# POWER.net
KiCad netlist of a schematic drawn in Altium Designer
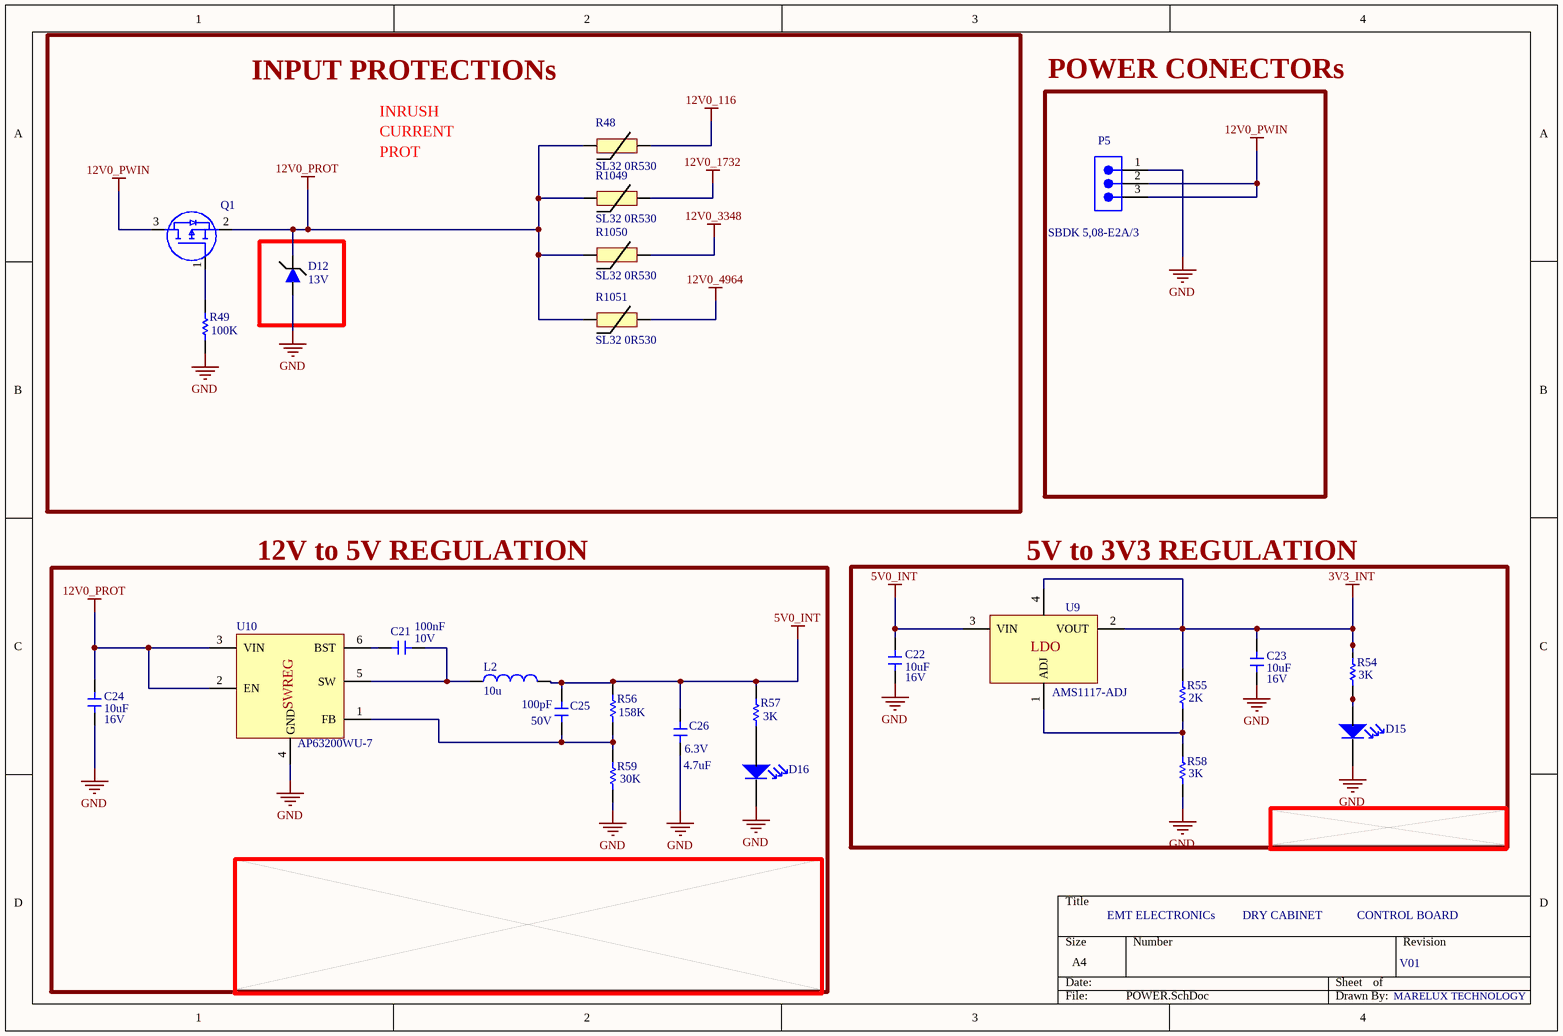
[diagram p0: POWER.SchDoc]

(export (version "E")
  (design (tool "Eeschema 10.0.6"))
  (components
    (comp (ref "C21")
      (value "100nF")
      (footprint "CAP_0402_CER")
      (description "Generic")
      (fields (field (name "PART NUMBER") "CL05B104KP5NNNC") (field (name "VOLTAGE") "10V"))
      (libsource (lib "MareLux24Lib") (part "CAP_GEN_CER"))
    )
    (comp (ref "C22")
      (value "10uF")
      (footprint "CAP_0805_CER")
      (description "10uF 0805 Ceramic Capacitor")
      (fields (field (name "PART NUMBER") "CL21A106KOQNNNE") (field (name "VOLTAGE") "16V"))
      (libsource (lib "MareLux24Lib") (part "CAP_GEN_CER"))
    )
    (comp (ref "C23")
      (value "10uF")
      (footprint "CAP_0805_CER")
      (description "10uF 0805 Ceramic Capacitor")
      (fields (field (name "PART NUMBER") "CL21A106KOQNNNE") (field (name "VOLTAGE") "16V"))
      (libsource (lib "MareLux24Lib") (part "CAP_GEN_CER"))
    )
    (comp (ref "C24")
      (value "10uF")
      (footprint "CAP_0805_CER")
      (description "10uF 0805 Ceramic Capacitor")
      (fields (field (name "PART NUMBER") "CL21A106KOQNNNE") (field (name "VOLTAGE") "16V"))
      (libsource (lib "MareLux24Lib") (part "CAP_GEN_CER"))
    )
    (comp (ref "C25")
      (value "100pF")
      (footprint "CAP_0402_CER")
      (description "Generic")
      (fields (field (name "PART NUMBER") "CC0402JRNPO9BN101") (field (name "VOLTAGE") "50V"))
      (libsource (lib "MareLux24Lib") (part "CAP_GEN_CER"))
    )
    (comp (ref "C26")
      (value "4.7uF")
      (footprint "CAP_0402_CER")
      (description "Generic")
      (fields (field (name "PART NUMBER") "CL10A475KP8NNNC") (field (name "VOLTAGE") "6.3V"))
      (libsource (lib "MareLux24Lib") (part "CAP_GEN_CER"))
    )
    (comp (ref "D12")
      (value "13V")
      (footprint "SOD-123F")
      (description "TVS DIODE 200W 14.4V-15.9V SOD-123")
      (fields (field (name "PART NUMBER") "SMF13A") (field (name "VOLTAGE") "14.4V"))
      (libsource (lib "MareLux24Lib") (part "SMF13A"))
    )
    (comp (ref "D15")
      (value "HSMM-C170")
      (footprint "LED_0805_SMD")
      (fields (field (name "VOLTAGE") "3.3V") (field (name "MANUFACTURER") "Broadcom"))
      (libsource (lib "MareLux24Lib") (part "LED_GEN"))
    )
    (comp (ref "D16")
      (value "HSMM-C170")
      (footprint "LED_0805_SMD")
      (fields (field (name "VOLTAGE") "3.3V") (field (name "MANUFACTURER") "Broadcom"))
      (libsource (lib "MareLux24Lib") (part "LED_GEN"))
    )
    (comp (ref "L2")
      (value "10u")
      (footprint "IND_YAGEO")
      (description "FIXED IND 10UH 4A 68 MOHM SMD")
      (fields (field (name "PART NUMBER") "BMRB00060630100MA1") (field (name "TOLERANCE") "±20%"))
      (libsource (lib "MareLux24Lib") (part "BMRB00060630100MA1"))
    )
    (comp (ref "P5")
      (value "SBDK 5,08-E2A/3")
      (footprint "691311500003")
      (description "WR-TBL Series 311 Open Vertical PCB Header, THT, pitch 5.08mm, 03p")
      (fields (field (name "MANUFACTURER") "Wurth Elektronik"))
      (libsource (lib "Altium_WR-TBL_Pluggable Connector (rev25b)") (part "691311500003"))
    )
    (comp (ref "Q1")
      (value "SQM110P06-8M9L_GE3")
      (footprint "SQM110P06_MOSFET")
      (description "P-Channel 60 V 110A (Tc) 230W (Tc) Surface Mount TO-263 (D2PAK)")
      (fields (field (name "VOLTAGE") "20 V") (field (name "POWER") "110A"))
      (libsource (lib "MareLux24Lib") (part "SQM110P06-8M9L_GE3"))
    )
    (comp (ref "R48")
      (value "SL32 0R530")
      (footprint "SL32 0R530")
      (description "Inrush Current Limiter 500 mOhms ±20% 30 A 1.220\" (31.00mm)")
      (fields (field (name "TOLERANCE") "20") (field (name "MANUFACTURER") "Cantherm"))
      (libsource (lib "MareLux24Lib") (part "SL32 0R530"))
    )
    (comp (ref "R49")
      (value "100K")
      (footprint "RES_0402_SMD")
      (description "Generic Chip Res")
      (fields (field (name "PART NUMBER") "RMCF0402JT100K"))
      (libsource (lib "MareLux24Lib") (part "RES_GEN_SMD"))
    )
    (comp (ref "R54")
      (value "3K")
      (footprint "RES_0402_SMD")
      (description "Generic Chip Res")
      (fields (field (name "PART NUMBER") "RMCF0402FT3K00"))
      (libsource (lib "MareLux24Lib") (part "RES_GEN_SMD"))
    )
    (comp (ref "R55")
      (value "2K")
      (footprint "RES_0402_SMD")
      (description "Generic Chip Res")
      (fields (field (name "PART NUMBER") "RMCF0402FT2K00"))
      (libsource (lib "MareLux24Lib") (part "RES_GEN_SMD"))
    )
    (comp (ref "R56")
      (value "158K")
      (footprint "RES_0402_SMD")
      (description "Generic Chip Res")
      (fields (field (name "PART NUMBER") "RMCF0402FT158K"))
      (libsource (lib "MareLux24Lib") (part "RES_GEN_SMD"))
    )
    (comp (ref "R57")
      (value "3K")
      (footprint "RES_0402_SMD")
      (description "Generic Chip Res")
      (fields (field (name "PART NUMBER") "RMCF0402FT3K00"))
      (libsource (lib "MareLux24Lib") (part "RES_GEN_SMD"))
    )
    (comp (ref "R58")
      (value "3K")
      (footprint "RES_0402_SMD")
      (description "Generic Chip Res")
      (fields (field (name "PART NUMBER") "RMCF0402FT3K00"))
      (libsource (lib "MareLux24Lib") (part "RES_GEN_SMD"))
    )
    (comp (ref "R59")
      (value "30K")
      (footprint "RES_0402_SMD")
      (description "Generic Chip Res")
      (libsource (lib "MareLux24Lib") (part "RES_GEN_SMD"))
    )
    (comp (ref "R1049")
      (value "SL32 0R530")
      (footprint "SL32 0R530")
      (description "Inrush Current Limiter 500 mOhms ±20% 30 A 1.220\" (31.00mm)")
      (fields (field (name "TOLERANCE") "20") (field (name "MANUFACTURER") "Cantherm"))
      (libsource (lib "MareLux24Lib") (part "SL32 0R530"))
    )
    (comp (ref "R1050")
      (value "SL32 0R530")
      (footprint "SL32 0R530")
      (description "Inrush Current Limiter 500 mOhms ±20% 30 A 1.220\" (31.00mm)")
      (fields (field (name "TOLERANCE") "20") (field (name "MANUFACTURER") "Cantherm"))
      (libsource (lib "MareLux24Lib") (part "SL32 0R530"))
    )
    (comp (ref "R1051")
      (value "SL32 0R530")
      (footprint "SL32 0R530")
      (description "Inrush Current Limiter 500 mOhms ±20% 30 A 1.220\" (31.00mm)")
      (fields (field (name "TOLERANCE") "20") (field (name "MANUFACTURER") "Cantherm"))
      (libsource (lib "MareLux24Lib") (part "SL32 0R530"))
    )
    (comp (ref "U9")
      (value "AMS1117-ADJ")
      (footprint "SOT-223-3")
      (description "IC LDO REG ADJ 1A SOT223")
      (fields (field (name "VOLTAGE") "ADJ") (field (name "MANUFACTURER") "EVVO"))
      (libsource (lib "MareLux24Lib") (part "AMS1117-ADJ"))
    )
    (comp (ref "U10")
      (value "AP63200WU-7")
      (footprint "TSOT-23-6")
      (description "IC REG BUCK ADJ 2A TSOT23-6\r\n3.8V to 32V")
      (fields (field (name "VOLTAGE") "ADJ") (field (name "MANUFACTURER") "Diodes Incorporated"))
      (libsource (lib "MareLux24Lib") (part "AP63200WU-7"))
    )
  )
  (nets
    (net (code "1") (name "3V3_INT") (class "Default")
      (node (ref "C23") (pin "2") (pinfunction "2_2") (pintype "passive"))
      (node (ref "R54") (pin "2") (pinfunction "2_2") (pintype "passive"))
      (node (ref "R55") (pin "2") (pinfunction "2_2") (pintype "passive"))
      (node (ref "U9") (pin "2") (pinfunction "VOUT_2") (pintype "power_in"))
      (node (ref "U9") (pin "4") (pinfunction "OUT_4") (pintype "power_in"))
    )
    (net (code "2") (name "5V0_INT") (class "Default")
      (node (ref "C22") (pin "2") (pinfunction "2_2") (pintype "passive"))
      (node (ref "C25") (pin "2") (pinfunction "2_2") (pintype "passive"))
      (node (ref "C26") (pin "2") (pinfunction "2_2") (pintype "passive"))
      (node (ref "L2") (pin "2") (pinfunction "2_2") (pintype "passive"))
      (node (ref "R56") (pin "2") (pinfunction "2_2") (pintype "passive"))
      (node (ref "R57") (pin "2") (pinfunction "2_2") (pintype "passive"))
      (node (ref "U9") (pin "3") (pinfunction "VIN_3") (pintype "power_in"))
    )
    (net (code "3") (name "12V0_116") (class "Default")
      (node (ref "R48") (pin "2") (pinfunction "2_2") (pintype "passive"))
    )
    (net (code "4") (name "12V0_1732") (class "Default")
      (node (ref "R1049") (pin "2") (pinfunction "2_2") (pintype "passive"))
    )
    (net (code "5") (name "12V0_3348") (class "Default")
      (node (ref "R1050") (pin "2") (pinfunction "2_2") (pintype "passive"))
    )
    (net (code "6") (name "12V0_4964") (class "Default")
      (node (ref "R1051") (pin "2") (pinfunction "2_2") (pintype "passive"))
    )
    (net (code "7") (name "12V0_PROT") (class "Default")
      (node (ref "C24") (pin "2") (pinfunction "2_2") (pintype "passive"))
      (node (ref "D12") (pin "1") (pinfunction "C_1") (pintype "passive"))
      (node (ref "Q1") (pin "2") (pinfunction "S_2") (pintype "passive"))
      (node (ref "R1049") (pin "1") (pinfunction "1_1") (pintype "passive"))
      (node (ref "R1050") (pin "1") (pinfunction "1_1") (pintype "passive"))
      (node (ref "R1051") (pin "1") (pinfunction "1_1") (pintype "passive"))
      (node (ref "R48") (pin "1") (pinfunction "1_1") (pintype "passive"))
      (node (ref "U10") (pin "2") (pinfunction "EN_2") (pintype "passive"))
      (node (ref "U10") (pin "3") (pinfunction "VIN_3") (pintype "passive"))
    )
    (net (code "8") (name "12V0_PWIN") (class "Default")
      (node (ref "P5") (pin "2") (pinfunction "2_2") (pintype "passive"))
      (node (ref "P5") (pin "3") (pinfunction "3_3") (pintype "passive"))
      (node (ref "Q1") (pin "3") (pinfunction "D_3") (pintype "passive"))
    )
    (net (code "9") (name "GND") (class "Default")
      (node (ref "C22") (pin "1") (pinfunction "1_1") (pintype "passive"))
      (node (ref "C23") (pin "1") (pinfunction "1_1") (pintype "passive"))
      (node (ref "C24") (pin "1") (pinfunction "1_1") (pintype "passive"))
      (node (ref "C26") (pin "1") (pinfunction "1_1") (pintype "passive"))
      (node (ref "D12") (pin "2") (pinfunction "A_2") (pintype "passive"))
      (node (ref "D15") (pin "C") (pinfunction "C_C") (pintype "passive"))
      (node (ref "D16") (pin "C") (pinfunction "C_C") (pintype "passive"))
      (node (ref "P5") (pin "1") (pinfunction "1_1") (pintype "passive"))
      (node (ref "R49") (pin "1") (pinfunction "1_1") (pintype "passive"))
      (node (ref "R58") (pin "1") (pinfunction "1_1") (pintype "passive"))
      (node (ref "R59") (pin "1") (pinfunction "1_1") (pintype "passive"))
      (node (ref "U10") (pin "4") (pinfunction "GND_4") (pintype "power_in"))
    )
    (net (code "10") (name "Net-(D15-PadA)") (class "Default")
      (node (ref "D15") (pin "A") (pinfunction "A_A") (pintype "passive"))
      (node (ref "R54") (pin "1") (pinfunction "1_1") (pintype "passive"))
    )
    (net (code "11") (name "Net-(D16-PadA)") (class "Default")
      (node (ref "D16") (pin "A") (pinfunction "A_A") (pintype "passive"))
      (node (ref "R57") (pin "1") (pinfunction "1_1") (pintype "passive"))
    )
    (net (code "12") (name "Net-(Q1-G)") (class "Default")
      (node (ref "Q1") (pin "1") (pinfunction "G_1") (pintype "passive"))
      (node (ref "R49") (pin "2") (pinfunction "2_2") (pintype "passive"))
    )
    (net (code "13") (name "Net-(U9-ADJ)") (class "Default")
      (node (ref "R55") (pin "1") (pinfunction "1_1") (pintype "passive"))
      (node (ref "R58") (pin "2") (pinfunction "2_2") (pintype "passive"))
      (node (ref "U9") (pin "1") (pinfunction "ADJ_1") (pintype "power_in"))
    )
    (net (code "14") (name "Net-(U10-BST)") (class "Default")
      (node (ref "C21") (pin "1") (pinfunction "1_1") (pintype "passive"))
      (node (ref "U10") (pin "6") (pinfunction "BST_6") (pintype "passive"))
    )
    (net (code "15") (name "Net-(U10-FB)") (class "Default")
      (node (ref "C25") (pin "1") (pinfunction "1_1") (pintype "passive"))
      (node (ref "R56") (pin "1") (pinfunction "1_1") (pintype "passive"))
      (node (ref "R59") (pin "2") (pinfunction "2_2") (pintype "passive"))
      (node (ref "U10") (pin "1") (pinfunction "FB_1") (pintype "passive"))
    )
    (net (code "16") (name "Net-(U10-SW)") (class "Default")
      (node (ref "C21") (pin "2") (pinfunction "2_2") (pintype "passive"))
      (node (ref "L2") (pin "1") (pinfunction "1_1") (pintype "passive"))
      (node (ref "U10") (pin "5") (pinfunction "SW_5") (pintype "passive"))
    )
  )
)
